# power_shield.net
KiCad netlist of a schematic drawn in EAGLE
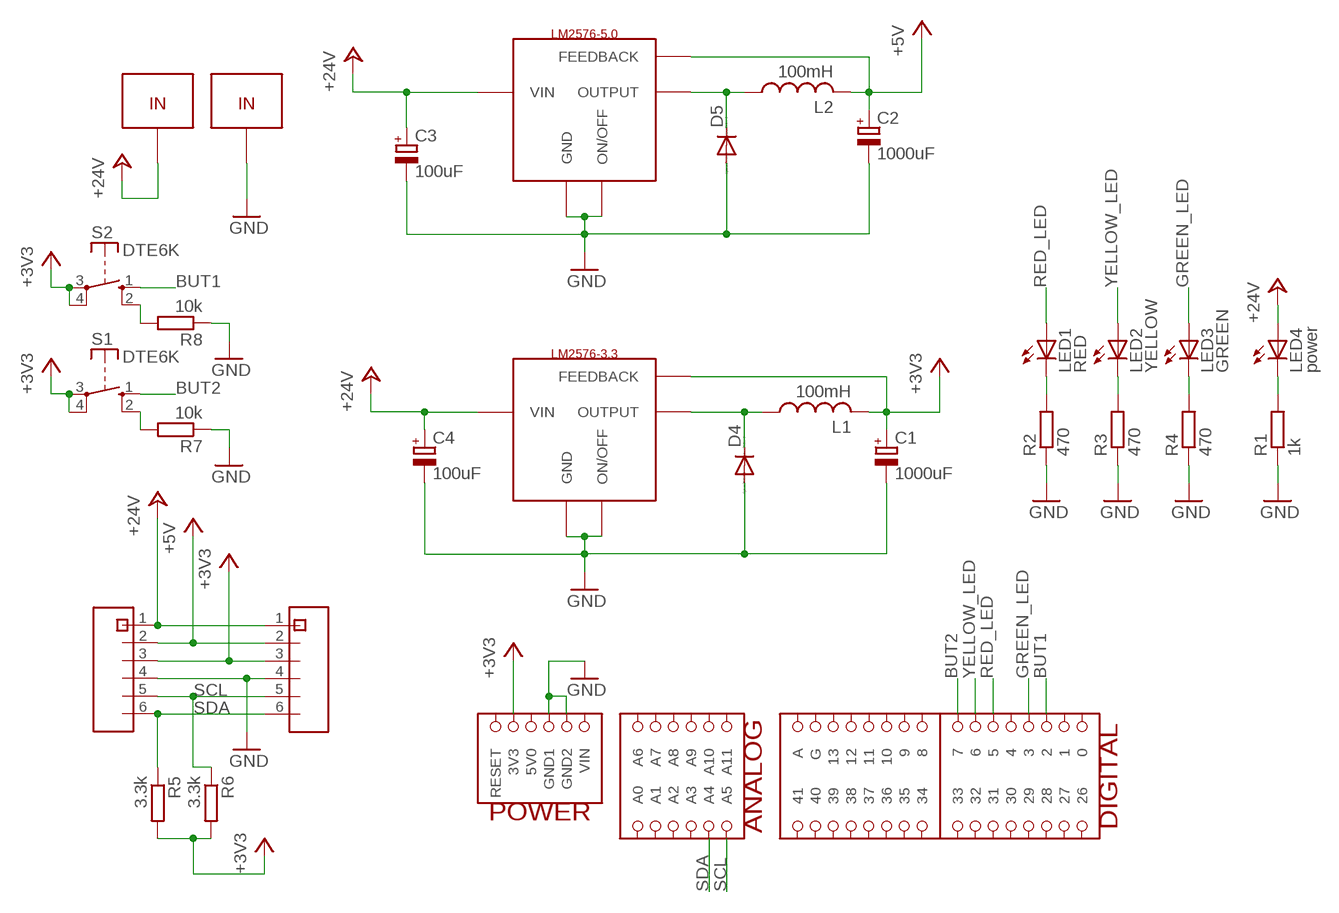
[diagram p0: schematic, sheet 1]

(export (version "E")
  (design (tool "Eeschema 10.0.6"))
  (components
    (comp (ref "C1")
      (value "1000uF")
      (footprint "eagle-import:150CLZ-1010")
      (libsource (lib "eagle-import") (part "CPOL-EU150CLZ-1010"))
    )
    (comp (ref "C2")
      (value "1000uF")
      (footprint "eagle-import:150CLZ-1010")
      (libsource (lib "eagle-import") (part "CPOL-EU150CLZ-1010"))
    )
    (comp (ref "C3")
      (value "100uF")
      (footprint "eagle-import:150CLZ-1010")
      (libsource (lib "eagle-import") (part "CPOL-EU150CLZ-1010"))
    )
    (comp (ref "C4")
      (value "100uF")
      (footprint "eagle-import:150CLZ-1010")
      (libsource (lib "eagle-import") (part "CPOL-EU150CLZ-1010"))
    )
    (comp (ref "D4")
      (value "DIODE-DO214AA")
      (footprint "eagle-import:DO214AA")
      (libsource (lib "eagle-import") (part "DIODE-DO214AA"))
    )
    (comp (ref "D5")
      (value "DIODE-DO214AA")
      (footprint "eagle-import:DO214AA")
      (libsource (lib "eagle-import") (part "DIODE-DO214AA"))
    )
    (comp (ref "L1")
      (value "100mH")
      (footprint "eagle-import:6000-XXXX-RC")
      (libsource (lib "eagle-import") (part "L-US6000-XXX-RC"))
    )
    (comp (ref "L2")
      (value "100mH")
      (footprint "eagle-import:6000-XXXX-RC")
      (libsource (lib "eagle-import") (part "L-US6000-XXX-RC"))
    )
    (comp (ref "LED1")
      (value "RED")
      (footprint "eagle-import:CHIPLED_1206")
      (libsource (lib "eagle-import") (part "LEDCHIPLED_1206"))
    )
    (comp (ref "LED2")
      (value "YELLOW")
      (footprint "eagle-import:CHIPLED_1206")
      (libsource (lib "eagle-import") (part "LEDCHIPLED_1206"))
    )
    (comp (ref "LED3")
      (value "GREEN")
      (footprint "eagle-import:CHIPLED_1206")
      (libsource (lib "eagle-import") (part "LEDCHIPLED_1206"))
    )
    (comp (ref "LED4")
      (value "power")
      (footprint "eagle-import:CHIPLED_1206")
      (libsource (lib "eagle-import") (part "LEDCHIPLED_1206"))
    )
    (comp (ref "R1")
      (value "1k")
      (footprint "eagle-import:R0603")
      (libsource (lib "eagle-import") (part "R-EU_R0603"))
    )
    (comp (ref "R2")
      (value "470")
      (footprint "eagle-import:R0603")
      (libsource (lib "eagle-import") (part "R-EU_R0603"))
    )
    (comp (ref "R3")
      (value "470")
      (footprint "eagle-import:R0603")
      (libsource (lib "eagle-import") (part "R-EU_R0603"))
    )
    (comp (ref "R4")
      (value "470")
      (footprint "eagle-import:R0603")
      (libsource (lib "eagle-import") (part "R-EU_R0603"))
    )
    (comp (ref "R5")
      (value "3.3k")
      (footprint "eagle-import:R0603")
      (libsource (lib "eagle-import") (part "R-EU_R0603"))
    )
    (comp (ref "R6")
      (value "3.3k")
      (footprint "eagle-import:R0603")
      (libsource (lib "eagle-import") (part "R-EU_R0603"))
    )
    (comp (ref "R7")
      (value "10k")
      (footprint "eagle-import:R0603")
      (libsource (lib "eagle-import") (part "R-EU_R0603"))
    )
    (comp (ref "R8")
      (value "10k")
      (footprint "eagle-import:R0603")
      (libsource (lib "eagle-import") (part "R-EU_R0603"))
    )
    (comp (ref "S1")
      (value "DTE6K")
      (footprint "eagle-import:DTE6K")
      (libsource (lib "eagle-import") (part "DTE6K"))
    )
    (comp (ref "S2")
      (value "DTE6K")
      (footprint "eagle-import:DTE6K")
      (libsource (lib "eagle-import") (part "DTE6K"))
    )
    (comp (ref "U$1")
      (value "UNO32_SHIELD")
      (footprint "eagle-import:UNO32_SHIELD")
      (libsource (lib "eagle-import") (part "UNO32_SHIELD"))
    )
    (comp (ref "U$2")
      (value "LM2576-5.0")
      (footprint "eagle-import:TO-220-5")
      (libsource (lib "eagle-import") (part "LM2576-5.0"))
    )
    (comp (ref "U$3")
      (value "LM2576-3.3")
      (footprint "eagle-import:TO-220-5")
      (libsource (lib "eagle-import") (part "LM2576-3.3"))
    )
    (comp (ref "U$4")
      (value "MOLEX_3.96MM_6P")
      (footprint "eagle-import:MOLEX_3.96MM_6P")
      (libsource (lib "eagle-import") (part "MOLEX_3.96MM_6P"))
    )
    (comp (ref "U$5")
      (value "MOLEX_3.96MM_6P")
      (footprint "eagle-import:MOLEX_3.96MM_6P")
      (libsource (lib "eagle-import") (part "MOLEX_3.96MM_6P"))
    )
    (comp (ref "U$6")
      (value "LABBHYLSA")
      (footprint "eagle-import:LABBHYLSA")
      (libsource (lib "eagle-import") (part "LABBHYLSA"))
    )
    (comp (ref "U$7")
      (value "LABBHYLSA")
      (footprint "eagle-import:LABBHYLSA")
      (libsource (lib "eagle-import") (part "LABBHYLSA"))
    )
  )
  (nets
    (net (code "1") (name "+3V3") (class "Default")
      (node (ref "C1") (pin "+") (pinfunction "+_+") (pintype "passive"))
      (node (ref "L1") (pin "2") (pinfunction "2_2") (pintype "passive"))
      (node (ref "R5") (pin "2") (pinfunction "2_2") (pintype "passive"))
      (node (ref "R6") (pin "2") (pinfunction "2_2") (pintype "passive"))
      (node (ref "S1") (pin "3") (pinfunction "P_3") (pintype "passive"))
      (node (ref "S1") (pin "4") (pinfunction "P_4") (pintype "passive"))
      (node (ref "S2") (pin "3") (pinfunction "P_3") (pintype "passive"))
      (node (ref "S2") (pin "4") (pinfunction "P_4") (pintype "passive"))
      (node (ref "U$1") (pin "3V3") (pinfunction "3V3_3V3") (pintype "bidirectional"))
      (node (ref "U$3") (pin "4") (pinfunction "FEEDBACK_4") (pintype "bidirectional"))
      (node (ref "U$4") (pin "3") (pinfunction "3_3") (pintype "bidirectional"))
      (node (ref "U$5") (pin "3") (pinfunction "3_3") (pintype "bidirectional"))
    )
    (net (code "2") (name "+5V") (class "Default")
      (node (ref "C2") (pin "+") (pinfunction "+_+") (pintype "passive"))
      (node (ref "L2") (pin "2") (pinfunction "2_2") (pintype "passive"))
      (node (ref "U$2") (pin "4") (pinfunction "FEEDBACK_4") (pintype "bidirectional"))
      (node (ref "U$4") (pin "2") (pinfunction "2_2") (pintype "bidirectional"))
      (node (ref "U$5") (pin "2") (pinfunction "2_2") (pintype "bidirectional"))
    )
    (net (code "3") (name "+24V") (class "Default")
      (node (ref "C3") (pin "+") (pinfunction "+_+") (pintype "passive"))
      (node (ref "C4") (pin "+") (pinfunction "+_+") (pintype "passive"))
      (node (ref "LED4") (pin "A") (pinfunction "A_A") (pintype "passive"))
      (node (ref "U$2") (pin "1") (pinfunction "VIN_1") (pintype "bidirectional"))
      (node (ref "U$3") (pin "1") (pinfunction "VIN_1") (pintype "bidirectional"))
      (node (ref "U$4") (pin "1") (pinfunction "1_1") (pintype "bidirectional"))
      (node (ref "U$5") (pin "1") (pinfunction "1_1") (pintype "bidirectional"))
      (node (ref "U$6") (pin "IN") (pinfunction "IN_IN") (pintype "bidirectional"))
      (node (ref "U$6") (pin "IN2") (pinfunction "IN_IN2") (pintype "bidirectional"))
    )
    (net (code "4") (name "/BUT1") (class "Default")
      (node (ref "S2") (pin "1") (pinfunction "S_1") (pintype "passive"))
      (node (ref "U$1") (pin "2") (pinfunction "2_2") (pintype "bidirectional"))
    )
    (net (code "5") (name "/BUT2") (class "Default")
      (node (ref "S1") (pin "1") (pinfunction "S_1") (pintype "passive"))
      (node (ref "U$1") (pin "7") (pinfunction "7_7") (pintype "bidirectional"))
    )
    (net (code "6") (name "/GREEN_LED") (class "Default")
      (node (ref "LED3") (pin "A") (pinfunction "A_A") (pintype "passive"))
      (node (ref "U$1") (pin "3") (pinfunction "3_3") (pintype "bidirectional"))
    )
    (net (code "7") (name "/RED_LED") (class "Default")
      (node (ref "LED1") (pin "A") (pinfunction "A_A") (pintype "passive"))
      (node (ref "U$1") (pin "5") (pinfunction "5_5") (pintype "bidirectional"))
    )
    (net (code "8") (name "/SCL") (class "Default")
      (node (ref "R6") (pin "1") (pinfunction "1_1") (pintype "passive"))
      (node (ref "U$1") (pin "A5") (pinfunction "A5_A5") (pintype "bidirectional"))
      (node (ref "U$4") (pin "5") (pinfunction "5_5") (pintype "bidirectional"))
      (node (ref "U$5") (pin "5") (pinfunction "5_5") (pintype "bidirectional"))
    )
    (net (code "9") (name "/SDA") (class "Default")
      (node (ref "R5") (pin "1") (pinfunction "1_1") (pintype "passive"))
      (node (ref "U$1") (pin "A4") (pinfunction "A4_A4") (pintype "bidirectional"))
      (node (ref "U$4") (pin "6") (pinfunction "6_6") (pintype "bidirectional"))
      (node (ref "U$5") (pin "6") (pinfunction "6_6") (pintype "bidirectional"))
    )
    (net (code "10") (name "/YELLOW_LED") (class "Default")
      (node (ref "LED2") (pin "A") (pinfunction "A_A") (pintype "passive"))
      (node (ref "U$1") (pin "6") (pinfunction "6_6") (pintype "bidirectional"))
    )
    (net (code "11") (name "GND") (class "Default")
      (node (ref "C1") (pin "-") (pinfunction "-_-") (pintype "passive"))
      (node (ref "C2") (pin "-") (pinfunction "-_-") (pintype "passive"))
      (node (ref "C3") (pin "-") (pinfunction "-_-") (pintype "passive"))
      (node (ref "C4") (pin "-") (pinfunction "-_-") (pintype "passive"))
      (node (ref "D4") (pin "A") (pinfunction "A_A") (pintype "passive"))
      (node (ref "D5") (pin "A") (pinfunction "A_A") (pintype "passive"))
      (node (ref "R1") (pin "1") (pinfunction "1_1") (pintype "passive"))
      (node (ref "R2") (pin "1") (pinfunction "1_1") (pintype "passive"))
      (node (ref "R3") (pin "1") (pinfunction "1_1") (pintype "passive"))
      (node (ref "R4") (pin "1") (pinfunction "1_1") (pintype "passive"))
      (node (ref "R7") (pin "1") (pinfunction "1_1") (pintype "passive"))
      (node (ref "R8") (pin "1") (pinfunction "1_1") (pintype "passive"))
      (node (ref "U$1") (pin "GND1") (pinfunction "GND1_GND1") (pintype "bidirectional"))
      (node (ref "U$1") (pin "GND2") (pinfunction "GND2_GND2") (pintype "bidirectional"))
      (node (ref "U$2") (pin "3") (pinfunction "GND_3") (pintype "bidirectional"))
      (node (ref "U$2") (pin "5") (pinfunction "ON/OFF_5") (pintype "bidirectional"))
      (node (ref "U$3") (pin "3") (pinfunction "GND_3") (pintype "bidirectional"))
      (node (ref "U$3") (pin "5") (pinfunction "ON/OFF_5") (pintype "bidirectional"))
      (node (ref "U$4") (pin "4") (pinfunction "4_4") (pintype "bidirectional"))
      (node (ref "U$5") (pin "4") (pinfunction "4_4") (pintype "bidirectional"))
      (node (ref "U$7") (pin "IN") (pinfunction "IN_IN") (pintype "bidirectional"))
      (node (ref "U$7") (pin "IN2") (pinfunction "IN_IN2") (pintype "bidirectional"))
    )
    (net (code "12") (name "Net-(LED1-PadC)") (class "Default")
      (node (ref "LED1") (pin "C") (pinfunction "C_C") (pintype "passive"))
      (node (ref "R2") (pin "2") (pinfunction "2_2") (pintype "passive"))
    )
    (net (code "13") (name "Net-(LED2-PadC)") (class "Default")
      (node (ref "LED2") (pin "C") (pinfunction "C_C") (pintype "passive"))
      (node (ref "R3") (pin "2") (pinfunction "2_2") (pintype "passive"))
    )
    (net (code "14") (name "Net-(LED3-PadC)") (class "Default")
      (node (ref "LED3") (pin "C") (pinfunction "C_C") (pintype "passive"))
      (node (ref "R4") (pin "2") (pinfunction "2_2") (pintype "passive"))
    )
    (net (code "15") (name "Net-(LED4-PadC)") (class "Default")
      (node (ref "LED4") (pin "C") (pinfunction "C_C") (pintype "passive"))
      (node (ref "R1") (pin "2") (pinfunction "2_2") (pintype "passive"))
    )
    (net (code "16") (name "Net-(R7-Pad2)") (class "Default")
      (node (ref "R7") (pin "2") (pinfunction "2_2") (pintype "passive"))
      (node (ref "S1") (pin "2") (pinfunction "S_2") (pintype "passive"))
    )
    (net (code "17") (name "Net-(R8-Pad2)") (class "Default")
      (node (ref "R8") (pin "2") (pinfunction "2_2") (pintype "passive"))
      (node (ref "S2") (pin "2") (pinfunction "S_2") (pintype "passive"))
    )
    (net (code "18") (name "Net-(U$2-OUTPUT)") (class "Default")
      (node (ref "D5") (pin "C") (pinfunction "C_C") (pintype "passive"))
      (node (ref "L2") (pin "1") (pinfunction "1_1") (pintype "passive"))
      (node (ref "U$2") (pin "2") (pinfunction "OUTPUT_2") (pintype "bidirectional"))
    )
    (net (code "19") (name "Net-(U$3-OUTPUT)") (class "Default")
      (node (ref "D4") (pin "C") (pinfunction "C_C") (pintype "passive"))
      (node (ref "L1") (pin "1") (pinfunction "1_1") (pintype "passive"))
      (node (ref "U$3") (pin "2") (pinfunction "OUTPUT_2") (pintype "bidirectional"))
    )
    (net (code "20") (name "unconnected-(U$1-Pad0)") (class "Default")
      (node (ref "U$1") (pin "0") (pinfunction "0_0") (pintype "bidirectional"))
    )
    (net (code "21") (name "unconnected-(U$1-Pad1)") (class "Default")
      (node (ref "U$1") (pin "1") (pinfunction "1_1") (pintype "bidirectional"))
    )
    (net (code "22") (name "unconnected-(U$1-Pad4)") (class "Default")
      (node (ref "U$1") (pin "4") (pinfunction "4_4") (pintype "bidirectional"))
    )
    (net (code "23") (name "unconnected-(U$1-Pad5V0)") (class "Default")
      (node (ref "U$1") (pin "5V0") (pinfunction "5V0_5V0") (pintype "bidirectional"))
    )
    (net (code "24") (name "unconnected-(U$1-Pad8)") (class "Default")
      (node (ref "U$1") (pin "8") (pinfunction "8_8") (pintype "bidirectional"))
    )
    (net (code "25") (name "unconnected-(U$1-Pad9)") (class "Default")
      (node (ref "U$1") (pin "9") (pinfunction "9_9") (pintype "bidirectional"))
    )
    (net (code "26") (name "unconnected-(U$1-Pad10)") (class "Default")
      (node (ref "U$1") (pin "10") (pinfunction "10_10") (pintype "bidirectional"))
    )
    (net (code "27") (name "unconnected-(U$1-Pad11)") (class "Default")
      (node (ref "U$1") (pin "11") (pinfunction "11_11") (pintype "bidirectional"))
    )
    (net (code "28") (name "unconnected-(U$1-Pad12)") (class "Default")
      (node (ref "U$1") (pin "12") (pinfunction "12_12") (pintype "bidirectional"))
    )
    (net (code "29") (name "unconnected-(U$1-Pad13)") (class "Default")
      (node (ref "U$1") (pin "13") (pinfunction "13_13") (pintype "bidirectional"))
    )
    (net (code "30") (name "unconnected-(U$1-Pad26)") (class "Default")
      (node (ref "U$1") (pin "26") (pinfunction "26_26") (pintype "bidirectional"))
    )
    (net (code "31") (name "unconnected-(U$1-Pad27)") (class "Default")
      (node (ref "U$1") (pin "27") (pinfunction "27_27") (pintype "bidirectional"))
    )
    (net (code "32") (name "unconnected-(U$1-Pad28)") (class "Default")
      (node (ref "U$1") (pin "28") (pinfunction "28_28") (pintype "bidirectional"))
    )
    (net (code "33") (name "unconnected-(U$1-Pad29)") (class "Default")
      (node (ref "U$1") (pin "29") (pinfunction "29_29") (pintype "bidirectional"))
    )
    (net (code "34") (name "unconnected-(U$1-Pad30)") (class "Default")
      (node (ref "U$1") (pin "30") (pinfunction "30_30") (pintype "bidirectional"))
    )
    (net (code "35") (name "unconnected-(U$1-Pad31)") (class "Default")
      (node (ref "U$1") (pin "31") (pinfunction "31_31") (pintype "bidirectional"))
    )
    (net (code "36") (name "unconnected-(U$1-Pad32)") (class "Default")
      (node (ref "U$1") (pin "32") (pinfunction "32_32") (pintype "bidirectional"))
    )
    (net (code "37") (name "unconnected-(U$1-Pad33)") (class "Default")
      (node (ref "U$1") (pin "33") (pinfunction "33_33") (pintype "bidirectional"))
    )
    (net (code "38") (name "unconnected-(U$1-Pad34)") (class "Default")
      (node (ref "U$1") (pin "34") (pinfunction "34_34") (pintype "bidirectional"))
    )
    (net (code "39") (name "unconnected-(U$1-Pad35)") (class "Default")
      (node (ref "U$1") (pin "35") (pinfunction "35_35") (pintype "bidirectional"))
    )
    (net (code "40") (name "unconnected-(U$1-Pad36)") (class "Default")
      (node (ref "U$1") (pin "36") (pinfunction "36_36") (pintype "bidirectional"))
    )
    (net (code "41") (name "unconnected-(U$1-Pad37)") (class "Default")
      (node (ref "U$1") (pin "37") (pinfunction "37_37") (pintype "bidirectional"))
    )
    (net (code "42") (name "unconnected-(U$1-Pad38)") (class "Default")
      (node (ref "U$1") (pin "38") (pinfunction "38_38") (pintype "bidirectional"))
    )
    (net (code "43") (name "unconnected-(U$1-Pad39)") (class "Default")
      (node (ref "U$1") (pin "39") (pinfunction "39_39") (pintype "bidirectional"))
    )
    (net (code "44") (name "unconnected-(U$1-Pad40)") (class "Default")
      (node (ref "U$1") (pin "40") (pinfunction "40_40") (pintype "bidirectional"))
    )
    (net (code "45") (name "unconnected-(U$1-Pad41)") (class "Default")
      (node (ref "U$1") (pin "41") (pinfunction "41_41") (pintype "bidirectional"))
    )
    (net (code "46") (name "unconnected-(U$1-PadA)") (class "Default")
      (node (ref "U$1") (pin "A") (pinfunction "A_A") (pintype "bidirectional"))
    )
    (net (code "47") (name "unconnected-(U$1-PadA0)") (class "Default")
      (node (ref "U$1") (pin "A0") (pinfunction "A0_A0") (pintype "bidirectional"))
    )
    (net (code "48") (name "unconnected-(U$1-PadA1)") (class "Default")
      (node (ref "U$1") (pin "A1") (pinfunction "A1_A1") (pintype "bidirectional"))
    )
    (net (code "49") (name "unconnected-(U$1-PadA2)") (class "Default")
      (node (ref "U$1") (pin "A2") (pinfunction "A2_A2") (pintype "bidirectional"))
    )
    (net (code "50") (name "unconnected-(U$1-PadA3)") (class "Default")
      (node (ref "U$1") (pin "A3") (pinfunction "A3_A3") (pintype "bidirectional"))
    )
    (net (code "51") (name "unconnected-(U$1-PadA6)") (class "Default")
      (node (ref "U$1") (pin "A6") (pinfunction "A6_A6") (pintype "bidirectional"))
    )
    (net (code "52") (name "unconnected-(U$1-PadA7)") (class "Default")
      (node (ref "U$1") (pin "A7") (pinfunction "A7_A7") (pintype "bidirectional"))
    )
    (net (code "53") (name "unconnected-(U$1-PadA8)") (class "Default")
      (node (ref "U$1") (pin "A8") (pinfunction "A8_A8") (pintype "bidirectional"))
    )
    (net (code "54") (name "unconnected-(U$1-PadA9)") (class "Default")
      (node (ref "U$1") (pin "A9") (pinfunction "A9_A9") (pintype "bidirectional"))
    )
    (net (code "55") (name "unconnected-(U$1-PadA10)") (class "Default")
      (node (ref "U$1") (pin "A10") (pinfunction "A10_A10") (pintype "bidirectional"))
    )
    (net (code "56") (name "unconnected-(U$1-PadA11)") (class "Default")
      (node (ref "U$1") (pin "A11") (pinfunction "A11_A11") (pintype "bidirectional"))
    )
    (net (code "57") (name "unconnected-(U$1-PadG)") (class "Default")
      (node (ref "U$1") (pin "G") (pinfunction "G_G") (pintype "bidirectional"))
    )
    (net (code "58") (name "unconnected-(U$1-PadRESET)") (class "Default")
      (node (ref "U$1") (pin "RESET") (pinfunction "RESET_RESET") (pintype "bidirectional"))
    )
    (net (code "59") (name "unconnected-(U$1-PadVIN)") (class "Default")
      (node (ref "U$1") (pin "VIN") (pinfunction "VIN_VIN") (pintype "bidirectional"))
    )
  )
)
